# Main.net
KiCad netlist of a schematic drawn in Altium Designer
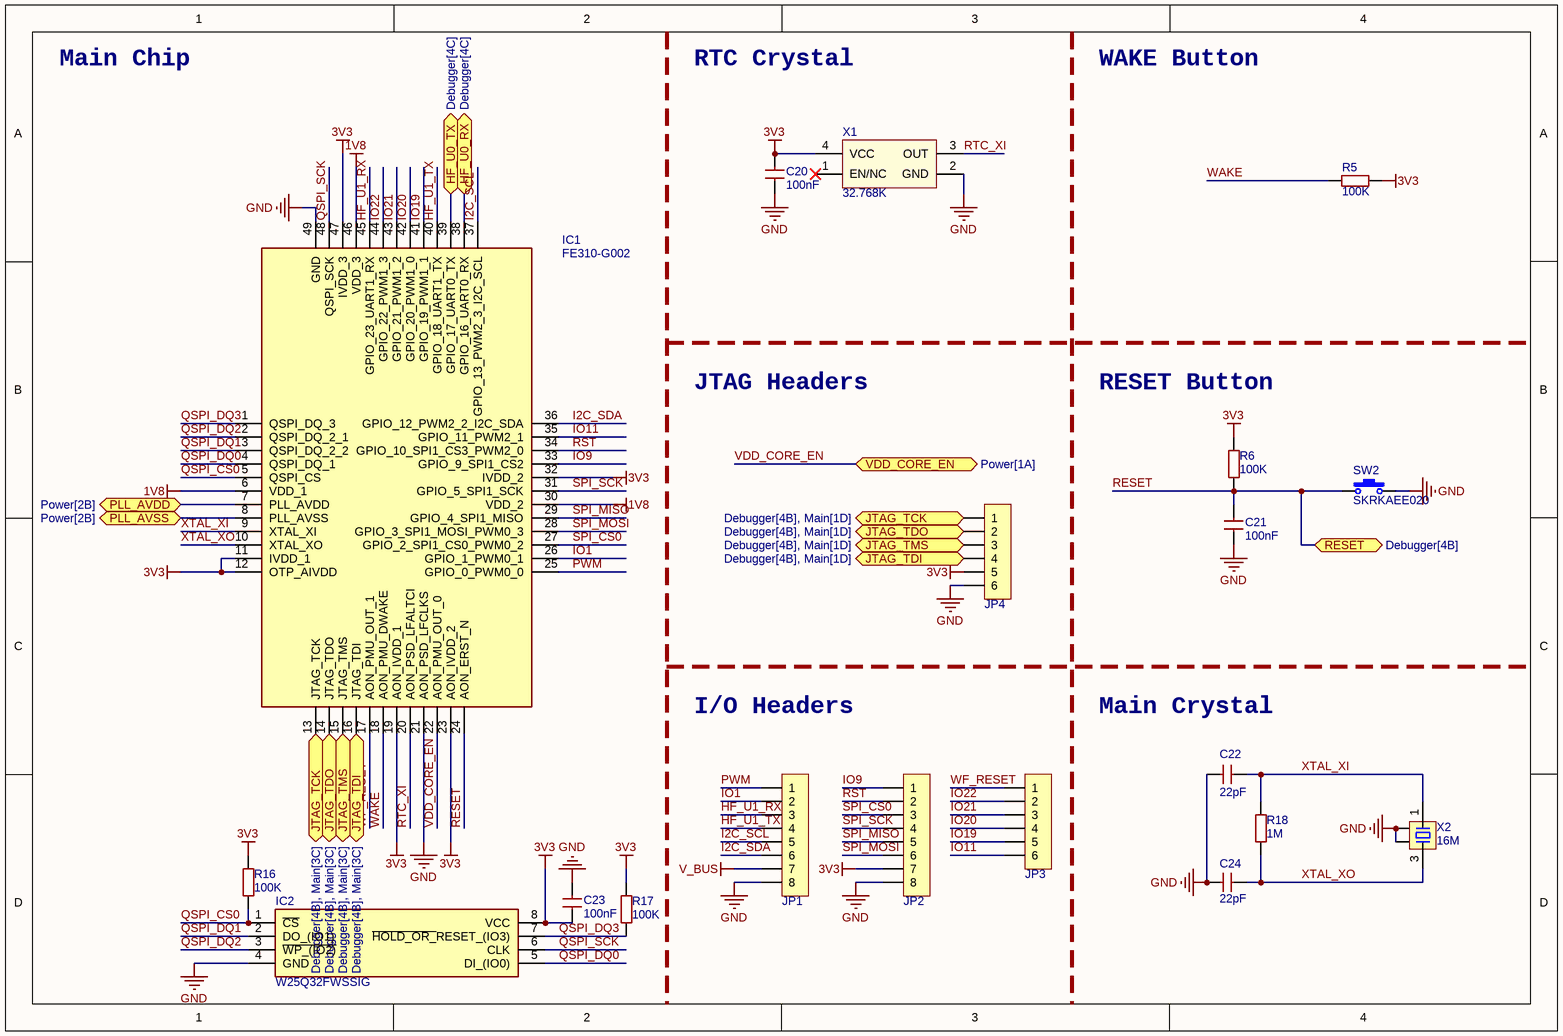
[diagram p0: Main.SchDoc]

(export (version "E")
  (design (tool "Eeschema 10.0.6"))
  (components
    (comp (ref "C20")
      (value "100nF")
      (footprint "C0603_NS")
      (description "贴片电容/MLCC电容")
      (libsource (lib "0.1 - 电阻-电容-电感-晶振-晶体-磁珠-电位器-法拉电容-馈通电容") (part "C"))
    )
    (comp (ref "C21")
      (value "100nF")
      (footprint "C0603_NS")
      (description "贴片电容/MLCC电容")
      (libsource (lib "0.1 - 电阻-电容-电感-晶振-晶体-磁珠-电位器-法拉电容-馈通电容") (part "C"))
    )
    (comp (ref "C22")
      (value "22pF")
      (footprint "C0603_NS")
      (description "贴片电容/MLCC电容")
      (libsource (lib "0.1 - 电阻-电容-电感-晶振-晶体-磁珠-电位器-法拉电容-馈通电容") (part "C"))
    )
    (comp (ref "C23")
      (value "100nF")
      (footprint "C0603_NS")
      (description "贴片电容/MLCC电容")
      (libsource (lib "0.1 - 电阻-电容-电感-晶振-晶体-磁珠-电位器-法拉电容-馈通电容") (part "C"))
    )
    (comp (ref "C24")
      (value "22pF")
      (footprint "C0603_NS")
      (description "贴片电容/MLCC电容")
      (libsource (lib "0.1 - 电阻-电容-电感-晶振-晶体-磁珠-电位器-法拉电容-馈通电容") (part "C"))
    )
    (comp (ref "IC1")
      (value "FE310-G002")
      (footprint "SamacSys:QFN40P600X600X93-49N")
      (description "Integrated Circuit")
      (libsource (lib "*") (part "FE310-G002"))
    )
    (comp (ref "IC2")
      (value "W25Q32FWSSIG")
      (footprint "SamacSys:SOIC127P790X216-8N")
      (description "Integrated Circuit")
      (fields (field (name "MOUSER PART NUMBER") "454-W25Q32FWSSIG"))
      (libsource (lib "*") (part "W25Q32FWSSIG"))
    )
    (comp (ref "JP1")
      (value "HDR-1X8")
      (footprint "HDR2.54-M-LI-8P")
      (description "8P接插件")
      (libsource (lib "5.5 - 2.54mm连接器(KF2EDGK_XH2.54_2.54排针排母)") (part "Header 8"))
    )
    (comp (ref "JP2")
      (value "HDR-1X8")
      (footprint "HDR2.54-M-LI-8P")
      (description "8P接插件")
      (libsource (lib "5.5 - 2.54mm连接器(KF2EDGK_XH2.54_2.54排针排母)") (part "Header 8"))
    )
    (comp (ref "JP3")
      (value "HDR-1X6")
      (footprint "HDR2.54-M-LI-6P")
      (description "6P接插件")
      (libsource (lib "5.5 - 2.54mm连接器(KF2EDGK_XH2.54_2.54排针排母)") (part "Header 6"))
    )
    (comp (ref "JP4")
      (value "HDR-1X6")
      (footprint "HDR2.54-M-LI-6P")
      (description "6P接插件")
      (libsource (lib "5.5 - 2.54mm连接器(KF2EDGK_XH2.54_2.54排针排母)") (part "Header 6"))
    )
    (comp (ref "R5")
      (value "100K")
      (footprint "R0603_NS")
      (description "贴片电阻")
      (libsource (lib "") (part "R_1"))
    )
    (comp (ref "R6")
      (value "100K")
      (footprint "R0603_NS")
      (description "贴片电阻")
      (libsource (lib "0.1 - 电阻-电容-电感-晶振-晶体-磁珠-电位器-法拉电容-馈通电容") (part "R"))
    )
    (comp (ref "R16")
      (value "100K")
      (footprint "R0603_NS")
      (description "贴片电阻")
      (libsource (lib "0.1 - 电阻-电容-电感-晶振-晶体-磁珠-电位器-法拉电容-馈通电容") (part "R"))
    )
    (comp (ref "R17")
      (value "100K")
      (footprint "R0603_NS")
      (description "贴片电阻")
      (libsource (lib "0.1 - 电阻-电容-电感-晶振-晶体-磁珠-电位器-法拉电容-馈通电容") (part "R"))
    )
    (comp (ref "R18")
      (value "1M")
      (footprint "R0603_NS")
      (description "贴片电阻")
      (libsource (lib "0.1 - 电阻-电容-电感-晶振-晶体-磁珠-电位器-法拉电容-馈通电容") (part "R"))
    )
    (comp (ref "SW2")
      (value "SKRKAEE020")
      (footprint "SKRKAEE020")
      (description "2.9x3.9轻触开关")
      (libsource (lib "0.5 - 按键_开关_蜂鸣器_保险丝_电池_测试点_Mark点_铜柱") (part "SKRKAEE020"))
    )
    (comp (ref "X1")
      (value "32.768K")
      (footprint "OSC-3225-4P")
      (description "4脚有源晶振(振荡器)")
      (libsource (lib "0.1 - 电阻-电容-电感-晶振-晶体-磁珠-电位器-法拉电容-馈通电容") (part "XTAL-ACT-4P"))
    )
    (comp (ref "X2")
      (value "16M")
      (footprint "XTAL-3225-4P")
      (description "4脚无源晶振(谐振器）")
      (libsource (lib "0.1 - 电阻-电容-电感-晶振-晶体-磁珠-电位器-法拉电容-馈通电容") (part "XTAL-4P"))
    )
  )
  (nets
    (net (code "1") (name "/HF_U0_RX") (class "Default")
      (node (ref "IC1") (pin "38") (pinfunction "GPIO_16_UART0_RX_38") (pintype "passive"))
    )
    (net (code "2") (name "/HF_U0_TX") (class "Default")
      (node (ref "IC1") (pin "39") (pinfunction "GPIO_17_UART0_TX_39") (pintype "passive"))
    )
    (net (code "3") (name "/HF_U1_RX") (class "Default")
      (node (ref "IC1") (pin "45") (pinfunction "GPIO_23_UART1_RX_45") (pintype "passive"))
      (node (ref "JP1") (pin "3") (pinfunction "3_3") (pintype "passive"))
    )
    (net (code "4") (name "/HF_U1_TX") (class "Default")
      (node (ref "IC1") (pin "40") (pinfunction "GPIO_18_UART1_TX_40") (pintype "passive"))
      (node (ref "JP1") (pin "4") (pinfunction "4_4") (pintype "passive"))
    )
    (net (code "5") (name "/I2C_SCL") (class "Default")
      (node (ref "IC1") (pin "37") (pinfunction "GPIO_13_PWM2_3_I2C_SCL_37") (pintype "passive"))
      (node (ref "JP1") (pin "5") (pinfunction "5_5") (pintype "passive"))
    )
    (net (code "6") (name "/I2C_SDA") (class "Default")
      (node (ref "IC1") (pin "36") (pinfunction "GPIO_12_PWM2_2_I2C_SDA_36") (pintype "passive"))
      (node (ref "JP1") (pin "6") (pinfunction "6_6") (pintype "passive"))
    )
    (net (code "7") (name "/IO1") (class "Default")
      (node (ref "IC1") (pin "26") (pinfunction "GPIO_1_PWM0_1_26") (pintype "passive"))
      (node (ref "JP1") (pin "2") (pinfunction "2_2") (pintype "passive"))
    )
    (net (code "8") (name "/IO9") (class "Default")
      (node (ref "IC1") (pin "33") (pinfunction "GPIO_9_SPI1_CS2_33") (pintype "passive"))
      (node (ref "JP2") (pin "1") (pinfunction "1_1") (pintype "passive"))
    )
    (net (code "9") (name "/IO11") (class "Default")
      (node (ref "IC1") (pin "35") (pinfunction "GPIO_11_PWM2_1_35") (pintype "passive"))
      (node (ref "JP3") (pin "6") (pinfunction "6_6") (pintype "passive"))
    )
    (net (code "10") (name "/IO19") (class "Default")
      (node (ref "IC1") (pin "41") (pinfunction "GPIO_19_PWM1_1_41") (pintype "passive"))
      (node (ref "JP3") (pin "5") (pinfunction "5_5") (pintype "passive"))
    )
    (net (code "11") (name "/IO20") (class "Default")
      (node (ref "IC1") (pin "42") (pinfunction "GPIO_20_PWM1_0_42") (pintype "passive"))
      (node (ref "JP3") (pin "4") (pinfunction "4_4") (pintype "passive"))
    )
    (net (code "12") (name "/IO21") (class "Default")
      (node (ref "IC1") (pin "43") (pinfunction "GPIO_21_PWM1_2_43") (pintype "passive"))
      (node (ref "JP3") (pin "3") (pinfunction "3_3") (pintype "passive"))
    )
    (net (code "13") (name "/IO22") (class "Default")
      (node (ref "IC1") (pin "44") (pinfunction "GPIO_22_PWM1_3_44") (pintype "passive"))
      (node (ref "JP3") (pin "2") (pinfunction "2_2") (pintype "passive"))
    )
    (net (code "14") (name "/JTAG_TCK") (class "Default")
      (node (ref "IC1") (pin "13") (pinfunction "JTAG_TCK_13") (pintype "passive"))
      (node (ref "JP4") (pin "1") (pinfunction "1_1") (pintype "passive"))
    )
    (net (code "15") (name "/JTAG_TDI") (class "Default")
      (node (ref "IC1") (pin "16") (pinfunction "JTAG_TDI_16") (pintype "passive"))
      (node (ref "JP4") (pin "4") (pinfunction "4_4") (pintype "passive"))
    )
    (net (code "16") (name "/JTAG_TDO") (class "Default")
      (node (ref "IC1") (pin "14") (pinfunction "JTAG_TDO_14") (pintype "passive"))
      (node (ref "JP4") (pin "2") (pinfunction "2_2") (pintype "passive"))
    )
    (net (code "17") (name "/JTAG_TMS") (class "Default")
      (node (ref "IC1") (pin "15") (pinfunction "JTAG_TMS_15") (pintype "passive"))
      (node (ref "JP4") (pin "3") (pinfunction "3_3") (pintype "passive"))
    )
    (net (code "18") (name "/PLL_AVDD") (class "Default")
      (node (ref "IC1") (pin "7") (pinfunction "PLL_AVDD_7") (pintype "passive"))
    )
    (net (code "19") (name "/PLL_AVSS") (class "Default")
      (node (ref "IC1") (pin "8") (pinfunction "PLL_AVSS_8") (pintype "passive"))
    )
    (net (code "20") (name "/PWM") (class "Default")
      (node (ref "IC1") (pin "25") (pinfunction "GPIO_0_PWM0_0_25") (pintype "passive"))
      (node (ref "JP1") (pin "1") (pinfunction "1_1") (pintype "passive"))
    )
    (net (code "21") (name "/QSPI_CS0") (class "Default")
      (node (ref "IC1") (pin "5") (pinfunction "QSPI_CS_5") (pintype "passive"))
      (node (ref "IC2") (pin "1") (pinfunction "~{CS}_1") (pintype "passive"))
      (node (ref "R16") (pin "1") (pinfunction "1_1") (pintype "passive"))
    )
    (net (code "22") (name "/QSPI_DQ0") (class "Default")
      (node (ref "IC1") (pin "4") (pinfunction "QSPI_DQ_1_4") (pintype "passive"))
      (node (ref "IC2") (pin "5") (pinfunction "DI_(IO0)_5") (pintype "passive"))
    )
    (net (code "23") (name "/QSPI_DQ1") (class "Default")
      (node (ref "IC1") (pin "3") (pinfunction "QSPI_DQ_2_2_3") (pintype "passive"))
      (node (ref "IC2") (pin "2") (pinfunction "DO_(IO1)_2") (pintype "passive"))
    )
    (net (code "24") (name "/QSPI_DQ2") (class "Default")
      (node (ref "IC1") (pin "2") (pinfunction "QSPI_DQ_2_1_2") (pintype "passive"))
      (node (ref "IC2") (pin "3") (pinfunction "~{WP_(IO2)}_3") (pintype "passive"))
    )
    (net (code "25") (name "/QSPI_DQ3") (class "Default")
      (node (ref "IC1") (pin "1") (pinfunction "QSPI_DQ_3_1") (pintype "passive"))
      (node (ref "IC2") (pin "7") (pinfunction "~{HOLD_OR_}RESET_(IO3)_7") (pintype "passive"))
      (node (ref "R17") (pin "1") (pinfunction "1_1") (pintype "passive"))
    )
    (net (code "26") (name "/QSPI_SCK") (class "Default")
      (node (ref "IC1") (pin "48") (pinfunction "QSPI_SCK_48") (pintype "passive"))
      (node (ref "IC2") (pin "6") (pinfunction "CLK_6") (pintype "passive"))
    )
    (net (code "27") (name "/RESET") (class "Default")
      (node (ref "C21") (pin "2") (pinfunction "2_2") (pintype "passive"))
      (node (ref "IC1") (pin "24") (pinfunction "AON_ERST_N_24") (pintype "passive"))
      (node (ref "R6") (pin "1") (pinfunction "1_1") (pintype "passive"))
      (node (ref "SW2") (pin "1") (pinfunction "1_1") (pintype "passive"))
    )
    (net (code "28") (name "/RST") (class "Default")
      (node (ref "IC1") (pin "34") (pinfunction "GPIO_10_SPI1_CS3_PWM2_0_34") (pintype "passive"))
      (node (ref "JP2") (pin "2") (pinfunction "2_2") (pintype "passive"))
    )
    (net (code "29") (name "/RTC_XI") (class "Default")
      (node (ref "IC1") (pin "20") (pinfunction "AON_PSD_LFALTCI_20") (pintype "passive"))
      (node (ref "X1") (pin "3") (pinfunction "OUT_3") (pintype "passive"))
    )
    (net (code "30") (name "/SPI_CS0") (class "Default")
      (node (ref "IC1") (pin "27") (pinfunction "GPIO_2_SPI1_CS0_PWM0_2_27") (pintype "passive"))
      (node (ref "JP2") (pin "3") (pinfunction "3_3") (pintype "passive"))
    )
    (net (code "31") (name "/SPI_MISO") (class "Default")
      (node (ref "IC1") (pin "29") (pinfunction "GPIO_4_SPI1_MISO_29") (pintype "passive"))
      (node (ref "JP2") (pin "5") (pinfunction "5_5") (pintype "passive"))
    )
    (net (code "32") (name "/SPI_MOSI") (class "Default")
      (node (ref "IC1") (pin "28") (pinfunction "GPIO_3_SPI1_MOSI_PWM0_3_28") (pintype "passive"))
      (node (ref "JP2") (pin "6") (pinfunction "6_6") (pintype "passive"))
    )
    (net (code "33") (name "/SPI_SCK") (class "Default")
      (node (ref "IC1") (pin "31") (pinfunction "GPIO_5_SPI1_SCK_31") (pintype "passive"))
      (node (ref "JP2") (pin "4") (pinfunction "4_4") (pintype "passive"))
    )
    (net (code "34") (name "/VDD_CORE_EN") (class "Default")
      (node (ref "IC1") (pin "22") (pinfunction "AON_PMU_OUT_0_22") (pintype "passive"))
    )
    (net (code "35") (name "/WAKE") (class "Default")
      (node (ref "IC1") (pin "18") (pinfunction "AON_PMU_DWAKE_18") (pintype "passive"))
      (node (ref "R5") (pin "1") (pinfunction "1_1") (pintype "passive"))
    )
    (net (code "36") (name "/WF_RESET") (class "Default")
      (node (ref "IC1") (pin "17") (pinfunction "AON_PMU_OUT_1_17") (pintype "passive"))
      (node (ref "JP3") (pin "1") (pinfunction "1_1") (pintype "passive"))
    )
    (net (code "37") (name "/XTAL_XI") (class "Default")
      (node (ref "C22") (pin "2") (pinfunction "2_2") (pintype "passive"))
      (node (ref "IC1") (pin "9") (pinfunction "XTAL_XI_9") (pintype "passive"))
      (node (ref "R18") (pin "2") (pinfunction "2_2") (pintype "passive"))
      (node (ref "X2") (pin "1") (pinfunction "1_1") (pintype "passive"))
    )
    (net (code "38") (name "/XTAL_XO") (class "Default")
      (node (ref "C24") (pin "1") (pinfunction "1_1") (pintype "passive"))
      (node (ref "IC1") (pin "10") (pinfunction "XTAL_XO_10") (pintype "passive"))
      (node (ref "R18") (pin "1") (pinfunction "1_1") (pintype "passive"))
      (node (ref "X2") (pin "3") (pinfunction "3_3") (pintype "passive"))
    )
    (net (code "39") (name "1V8") (class "Default")
      (node (ref "IC1") (pin "30") (pinfunction "VDD_2_30") (pintype "passive"))
      (node (ref "IC1") (pin "46") (pinfunction "VDD_3_46") (pintype "passive"))
      (node (ref "IC1") (pin "6") (pinfunction "VDD_1_6") (pintype "passive"))
    )
    (net (code "40") (name "3V3") (class "Default")
      (node (ref "C20") (pin "2") (pinfunction "2_2") (pintype "passive"))
      (node (ref "C23") (pin "1") (pinfunction "1_1") (pintype "passive"))
      (node (ref "IC1") (pin "11") (pinfunction "IVDD_1_11") (pintype "passive"))
      (node (ref "IC1") (pin "12") (pinfunction "OTP_AIVDD_12") (pintype "passive"))
      (node (ref "IC1") (pin "19") (pinfunction "AON_IVDD_1_19") (pintype "passive"))
      (node (ref "IC1") (pin "23") (pinfunction "AON_IVDD_2_23") (pintype "passive"))
      (node (ref "IC1") (pin "32") (pinfunction "IVDD_2_32") (pintype "passive"))
      (node (ref "IC1") (pin "47") (pinfunction "IVDD_3_47") (pintype "passive"))
      (node (ref "IC2") (pin "8") (pinfunction "VCC_8") (pintype "passive"))
      (node (ref "JP2") (pin "7") (pinfunction "7_7") (pintype "passive"))
      (node (ref "JP4") (pin "5") (pinfunction "5_5") (pintype "passive"))
      (node (ref "R16") (pin "2") (pinfunction "2_2") (pintype "passive"))
      (node (ref "R17") (pin "2") (pinfunction "2_2") (pintype "passive"))
      (node (ref "R5") (pin "2") (pinfunction "2_2") (pintype "passive"))
      (node (ref "R6") (pin "2") (pinfunction "2_2") (pintype "passive"))
      (node (ref "X1") (pin "4") (pinfunction "VCC_4") (pintype "passive"))
    )
    (net (code "41") (name "GND") (class "Default")
      (node (ref "C20") (pin "1") (pinfunction "1_1") (pintype "passive"))
      (node (ref "C21") (pin "1") (pinfunction "1_1") (pintype "passive"))
      (node (ref "C22") (pin "1") (pinfunction "1_1") (pintype "passive"))
      (node (ref "C23") (pin "2") (pinfunction "2_2") (pintype "passive"))
      (node (ref "C24") (pin "2") (pinfunction "2_2") (pintype "passive"))
      (node (ref "IC1") (pin "21") (pinfunction "AON_PSD_LFCLKS_21") (pintype "passive"))
      (node (ref "IC1") (pin "49") (pinfunction "GND_49") (pintype "passive"))
      (node (ref "IC2") (pin "4") (pinfunction "GND_4") (pintype "passive"))
      (node (ref "JP1") (pin "8") (pinfunction "8_8") (pintype "passive"))
      (node (ref "JP2") (pin "8") (pinfunction "8_8") (pintype "passive"))
      (node (ref "JP4") (pin "6") (pinfunction "6_6") (pintype "passive"))
      (node (ref "SW2") (pin "2") (pinfunction "2_2") (pintype "passive"))
      (node (ref "X1") (pin "2") (pinfunction "GND_2") (pintype "passive"))
      (node (ref "X2") (pin "2") (pinfunction "2_2") (pintype "passive"))
      (node (ref "X2") (pin "4") (pinfunction "4_4") (pintype "passive"))
    )
    (net (code "42") (name "V_BUS") (class "Default")
      (node (ref "JP1") (pin "7") (pinfunction "7_7") (pintype "passive"))
    )
    (net (code "43") (name "unconnected-(X1-EN{slash}NC-Pad1)") (class "Default")
      (node (ref "X1") (pin "1") (pinfunction "EN/NC_1") (pintype "passive+no_connect"))
    )
  )
)
